# MP1584_5V.net
KiCad netlist of a schematic drawn in Altium Designer
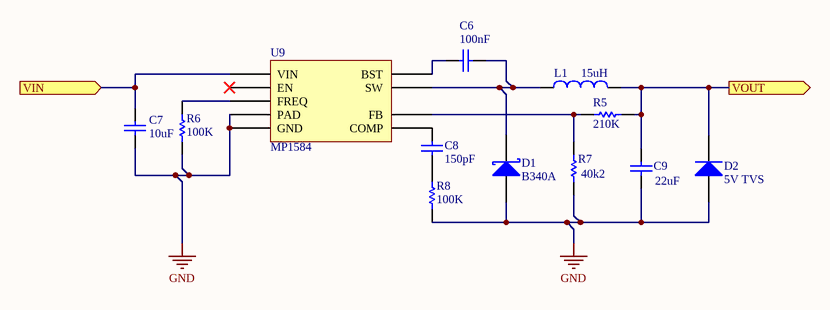
[diagram p0: MP1584_5V.SchDoc]

(export (version "E")
  (design (tool "Eeschema 10.0.6"))
  (components
    (comp (ref "C6")
      (value "100nF")
      (footprint "CAPC0603(1608)100_L")
      (description "CAP 100nF 50V ±5% 0603 (1608 Metric) Thickness 1mm SMD")
      (fields (field (name "TOLERANCE") "Â±5%"))
      (libsource (lib "Altium Content Vault") (part "CMP-1035-02591-1"))
    )
    (comp (ref "C7")
      (value "10uF")
      (footprint "CAPC1210(3225)280_L")
      (description "CAP 10uF 35V ±10% 1210 (3225 Metric) Thickness 2.8mm SMD")
      (fields (field (name "TOLERANCE") "Â±10%"))
      (libsource (lib "Altium Content Vault") (part "CMP-1038-02234-1"))
    )
    (comp (ref "C8")
      (value "150pF")
      (footprint "CAPC0603(1608)100_L")
      (description "CAP 150pF 50V ±5% 0603 (1608 Metric) Thickness 1mm SMD")
      (fields (field (name "TOLERANCE") "Â±5%"))
      (libsource (lib "Altium Content Vault") (part "CMP-1035-01367-1"))
    )
    (comp (ref "C9")
      (value "22uF")
      (footprint "CAPC1210(3225)170_L")
      (description "CAP 22uF 6.3V ±10% 1210 (3225 Metric) Thickness 1.7mm SMD")
      (fields (field (name "TOLERANCE") "Â±10%"))
      (libsource (lib "Altium Content Vault") (part "CMP-1038-02258-1"))
    )
    (comp (ref "D1")
      (value "B340A")
      (footprint "DIOD-SMA-2_V")
      (libsource (lib "Altium Content Vault") (part "CMP-1667-00003-1"))
    )
    (comp (ref "D2")
      (value "5V TVS")
      (footprint "VISH-DO-214AC-2_M")
      (fields
        (field (name "MANUFACTURER") "Vishay Semiconductor")
        (field (name "PARTNUMBER") "SMAJ5.0AHE3/61")
      )
      (libsource (lib "Altium Content Vault") (part "CMP-0548-00062-2"))
    )
    (comp (ref "L1")
      (value "15uH")
      (footprint "0630 Inductor")
      (description "0630 Inductor")
      (fields (field (name "PUBLISHER") "Altium Limited"))
      (libsource (lib "Components") (part "PCC-M0630M"))
    )
    (comp (ref "R5")
      (value "210K")
      (footprint "RESC0603(1608)_L")
      (description "210K 0.1W 1% 0603 (1608 Metric)  SMD")
      (fields (field (name "POWER") "0.1 W") (field (name "TOLERANCE") "1 %"))
      (libsource (lib "Altium Content Vault") (part "CMP-1012-00770-1"))
    )
    (comp (ref "R6")
      (value "100K")
      (footprint "RESC0603(1608)_L")
      (description "100K 0.1W 5% 0603 (1608 Metric)  SMD")
      (fields (field (name "TOLERANCE") "5 %") (field (name "POWER") "0.1 W"))
      (libsource (lib "Altium Content Vault") (part "CMP-1012-00122-1"))
    )
    (comp (ref "R7")
      (value "40k2")
      (footprint "RESC0603(1608)_L")
      (description "40K2 0.1W 1% 0603 (1608 Metric)  SMD")
      (fields (field (name "TOLERANCE") "1 %") (field (name "POWER") "0.1 W"))
      (libsource (lib "Altium Content Vault") (part "CMP-1012-00691-1"))
    )
    (comp (ref "R8")
      (value "100K")
      (footprint "RESC0603(1608)_L")
      (description "100K 0.1W 5% 0603 (1608 Metric)  SMD")
      (fields (field (name "TOLERANCE") "5 %") (field (name "POWER") "0.1 W"))
      (libsource (lib "Altium Content Vault") (part "CMP-1012-00122-1"))
    )
    (comp (ref "U9")
      (value "MP1584")
      (footprint "SOIC8E")
      (description "MP1584 3A, 1.5MHz, 28V Step-Down Converter")
      (libsource (lib "Components") (part "MP1584"))
    )
  )
  (nets
    (net (code "1") (name "/VIN") (class "Default")
      (node (ref "C7") (pin "2") (pinfunction "2_2") (pintype "passive"))
      (node (ref "U9") (pin "7") (pinfunction "VIN_7") (pintype "passive"))
    )
    (net (code "2") (name "/VOUT") (class "Default")
      (node (ref "C9") (pin "2") (pinfunction "2_2") (pintype "passive"))
      (node (ref "D2") (pin "1") (pinfunction "K_1") (pintype "passive"))
      (node (ref "L1") (pin "2") (pinfunction "2_2") (pintype "passive"))
      (node (ref "R5") (pin "2") (pinfunction "2_2") (pintype "passive"))
    )
    (net (code "3") (name "GND") (class "Default")
      (node (ref "C7") (pin "1") (pinfunction "1_1") (pintype "passive"))
      (node (ref "C9") (pin "1") (pinfunction "1_1") (pintype "passive"))
      (node (ref "D1") (pin "1") (pinfunction "A_1") (pintype "passive"))
      (node (ref "D2") (pin "2") (pinfunction "A_2") (pintype "passive"))
      (node (ref "R6") (pin "1") (pinfunction "1_1") (pintype "passive"))
      (node (ref "R7") (pin "1") (pinfunction "1_1") (pintype "passive"))
      (node (ref "R8") (pin "1") (pinfunction "1_1") (pintype "passive"))
      (node (ref "U9") (pin "5") (pinfunction "GND_5") (pintype "passive"))
      (node (ref "U9") (pin "9") (pinfunction "PAD_9") (pintype "passive"))
    )
    (net (code "4") (name "Net-(C8-Pad1)") (class "Default")
      (node (ref "C8") (pin "1") (pinfunction "1_1") (pintype "passive"))
      (node (ref "R8") (pin "2") (pinfunction "2_2") (pintype "passive"))
    )
    (net (code "5") (name "Net-(D1-K)") (class "Default")
      (node (ref "C6") (pin "2") (pinfunction "2_2") (pintype "passive"))
      (node (ref "D1") (pin "2") (pinfunction "K_2") (pintype "passive"))
      (node (ref "L1") (pin "1") (pinfunction "1_1") (pintype "passive"))
      (node (ref "U9") (pin "1") (pinfunction "SW_1") (pintype "passive"))
    )
    (net (code "6") (name "Net-(U9-BST)") (class "Default")
      (node (ref "C6") (pin "1") (pinfunction "1_1") (pintype "passive"))
      (node (ref "U9") (pin "8") (pinfunction "BST_8") (pintype "passive"))
    )
    (net (code "7") (name "Net-(U9-COMP)") (class "Default")
      (node (ref "C8") (pin "2") (pinfunction "2_2") (pintype "passive"))
      (node (ref "U9") (pin "3") (pinfunction "COMP_3") (pintype "passive"))
    )
    (net (code "8") (name "Net-(U9-FB)") (class "Default")
      (node (ref "R5") (pin "1") (pinfunction "1_1") (pintype "passive"))
      (node (ref "R7") (pin "2") (pinfunction "2_2") (pintype "passive"))
      (node (ref "U9") (pin "4") (pinfunction "FB_4") (pintype "passive"))
    )
    (net (code "9") (name "Net-(U9-FREQ)") (class "Default")
      (node (ref "R6") (pin "2") (pinfunction "2_2") (pintype "passive"))
      (node (ref "U9") (pin "6") (pinfunction "FREQ_6") (pintype "passive"))
    )
    (net (code "10") (name "unconnected-(U9-EN-Pad2)") (class "Default")
      (node (ref "U9") (pin "2") (pinfunction "EN_2") (pintype "passive+no_connect"))
    )
  )
)
